# MinimumSystem_Raihansyah_A_M__2150733407.net
KiCad netlist of a schematic drawn in EAGLE
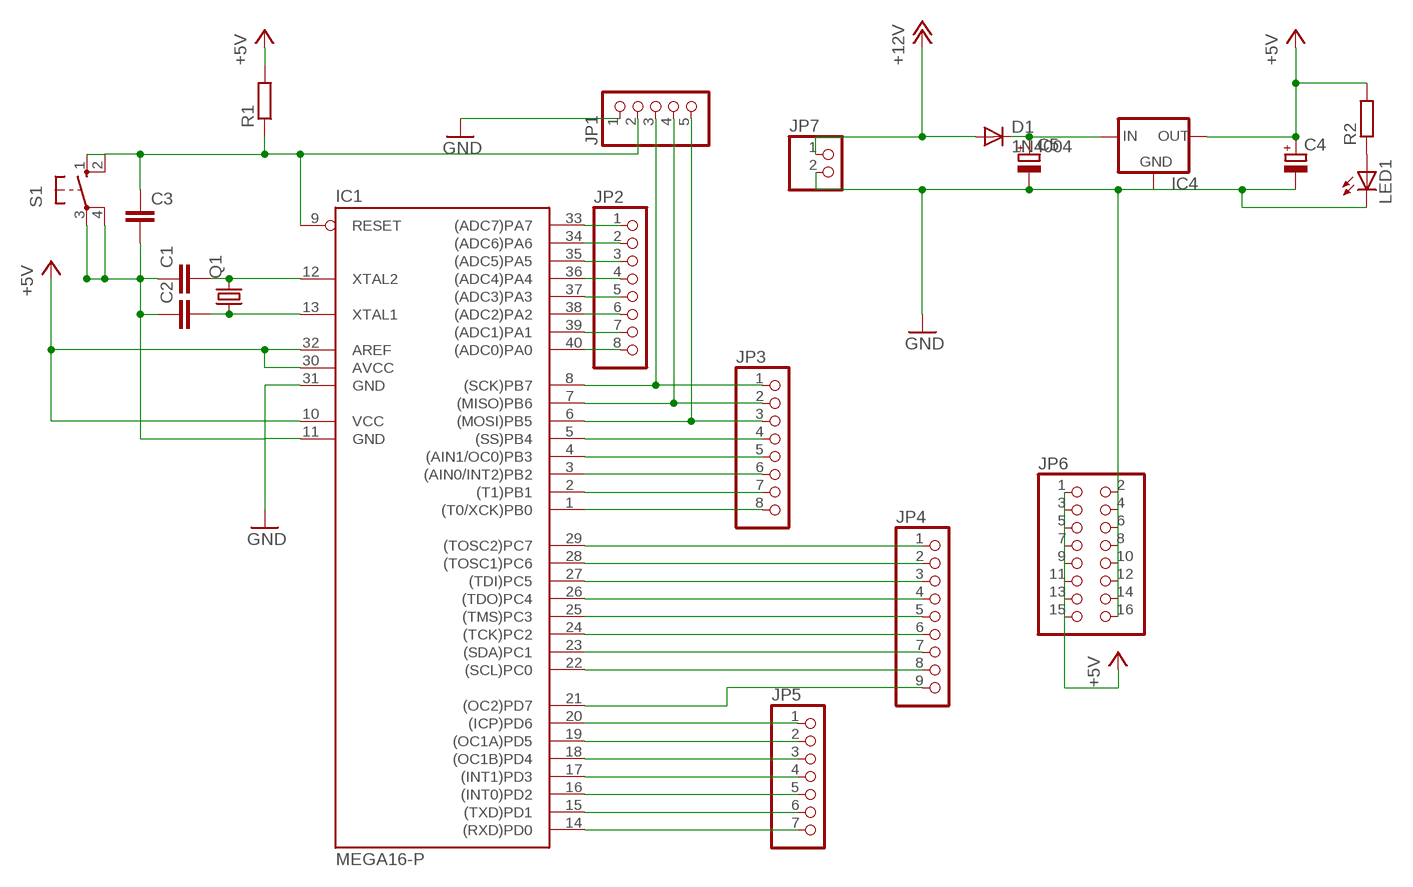
[diagram p0: schematic, sheet 1]

(export (version "E")
  (design (tool "Eeschema 10.0.6"))
  (components
    (comp (ref "C1")
      (value "C-EU025-024X044")
      (footprint "eagle-import:C025-024X044")
      (libsource (lib "eagle-import") (part "C-EU025-024X044"))
    )
    (comp (ref "C2")
      (value "C-EU025-024X044")
      (footprint "eagle-import:C025-024X044")
      (libsource (lib "eagle-import") (part "C-EU025-024X044"))
    )
    (comp (ref "C3")
      (value "C-EU050-025X075")
      (footprint "eagle-import:C050-025X075")
      (libsource (lib "eagle-import") (part "resistor_C-EU050-025X075"))
    )
    (comp (ref "C4")
      (value "CPOL-EUE2.5-5")
      (footprint "eagle-import:E2,5-5")
      (libsource (lib "eagle-import") (part "CPOL-EUE2.5-5"))
    )
    (comp (ref "C5")
      (value "CPOL-EUE2.5-5")
      (footprint "eagle-import:E2,5-5")
      (libsource (lib "eagle-import") (part "CPOL-EUE2.5-5"))
    )
    (comp (ref "D1")
      (value "1N4004")
      (footprint "eagle-import:DO41-10")
      (libsource (lib "eagle-import") (part "1N4004"))
    )
    (comp (ref "IC1")
      (value "MEGA16-P")
      (footprint "eagle-import:DIL40")
      (fields (field (name "MPN") "ATMEGA16-16PU"))
      (libsource (lib "eagle-import") (part "MEGA16-P"))
    )
    (comp (ref "IC4")
      (value "78XXS")
      (footprint "eagle-import:78XXS")
      (libsource (lib "eagle-import") (part "78XXS"))
    )
    (comp (ref "JP1")
      (value "PINHD-1X5")
      (footprint "eagle-import:1X05")
      (libsource (lib "eagle-import") (part "PINHD-1X5"))
    )
    (comp (ref "JP2")
      (value "PINHD-1X8")
      (footprint "eagle-import:1X08")
      (libsource (lib "eagle-import") (part "PINHD-1X8"))
    )
    (comp (ref "JP3")
      (value "PINHD-1X8")
      (footprint "eagle-import:1X08")
      (libsource (lib "eagle-import") (part "PINHD-1X8"))
    )
    (comp (ref "JP4")
      (value "PINHD-1X9")
      (footprint "eagle-import:1X09")
      (libsource (lib "eagle-import") (part "PINHD-1X9"))
    )
    (comp (ref "JP5")
      (value "PINHD-1X7")
      (footprint "eagle-import:1X07")
      (libsource (lib "eagle-import") (part "PINHD-1X7"))
    )
    (comp (ref "JP6")
      (value "PINHD-2X8")
      (footprint "eagle-import:2X08")
      (libsource (lib "eagle-import") (part "PINHD-2X8"))
    )
    (comp (ref "JP7")
      (value "PINHD-1X2")
      (footprint "eagle-import:1X02")
      (libsource (lib "eagle-import") (part "PINHD-1X2"))
    )
    (comp (ref "LED1")
      (value "LED5MM")
      (footprint "eagle-import:LED5MM")
      (libsource (lib "eagle-import") (part "LED5MM"))
    )
    (comp (ref "Q1")
      (value "CRYSTALHC49U-V")
      (footprint "eagle-import:HC49U-V")
      (libsource (lib "eagle-import") (part "CRYSTALHC49U-V"))
    )
    (comp (ref "R1")
      (value "R-EU_0204/7")
      (footprint "eagle-import:0204_7")
      (libsource (lib "eagle-import") (part "R-EU_0204/7"))
    )
    (comp (ref "R2")
      (value "R-EU_0204/7")
      (footprint "eagle-import:0204_7")
      (libsource (lib "eagle-import") (part "R-EU_0204/7"))
    )
    (comp (ref "S1")
      (value "10-XX")
      (footprint "eagle-import:B3F-10XX")
      (fields (field (name "MPN") "B3F-1000"))
      (libsource (lib "eagle-import") (part "10-XX"))
    )
  )
  (nets
    (net (code "1") (name "+5V") (class "Default")
      (node (ref "C4") (pin "+") (pinfunction "+_+") (pintype "passive"))
      (node (ref "IC1") (pin "10") (pinfunction "VCC_10") (pintype "power_in"))
      (node (ref "IC1") (pin "30") (pinfunction "AVCC_30") (pintype "power_in"))
      (node (ref "IC1") (pin "32") (pinfunction "AREF_32") (pintype "passive"))
      (node (ref "IC4") (pin "OUT") (pinfunction "OUT_OUT") (pintype "passive"))
      (node (ref "JP6") (pin "1") (pinfunction "1_1") (pintype "passive"))
      (node (ref "JP6") (pin "11") (pinfunction "11_11") (pintype "passive"))
      (node (ref "JP6") (pin "13") (pinfunction "13_13") (pintype "passive"))
      (node (ref "JP6") (pin "15") (pinfunction "15_15") (pintype "passive"))
      (node (ref "JP6") (pin "3") (pinfunction "3_3") (pintype "passive"))
      (node (ref "JP6") (pin "5") (pinfunction "5_5") (pintype "passive"))
      (node (ref "JP6") (pin "7") (pinfunction "7_7") (pintype "passive"))
      (node (ref "JP6") (pin "9") (pinfunction "9_9") (pintype "passive"))
      (node (ref "R1") (pin "2") (pinfunction "2_2") (pintype "passive"))
      (node (ref "R2") (pin "2") (pinfunction "2_2") (pintype "passive"))
    )
    (net (code "2") (name "+12V") (class "Default")
      (node (ref "D1") (pin "A") (pinfunction "A_A") (pintype "passive"))
      (node (ref "JP7") (pin "1") (pinfunction "1_1") (pintype "passive"))
    )
    (net (code "3") (name "GND") (class "Default")
      (node (ref "C1") (pin "1") (pinfunction "1_1") (pintype "passive"))
      (node (ref "C2") (pin "1") (pinfunction "1_1") (pintype "passive"))
      (node (ref "C3") (pin "2") (pinfunction "2_2") (pintype "passive"))
      (node (ref "C4") (pin "-") (pinfunction "-_-") (pintype "passive"))
      (node (ref "C5") (pin "-") (pinfunction "-_-") (pintype "passive"))
      (node (ref "IC1") (pin "11") (pinfunction "GND_11") (pintype "power_in"))
      (node (ref "IC1") (pin "31") (pinfunction "GND_31") (pintype "power_in"))
      (node (ref "IC4") (pin "GND") (pinfunction "GND_GND") (pintype "input"))
      (node (ref "JP1") (pin "1") (pinfunction "1_1") (pintype "passive"))
      (node (ref "JP6") (pin "10") (pinfunction "10_10") (pintype "passive"))
      (node (ref "JP6") (pin "12") (pinfunction "12_12") (pintype "passive"))
      (node (ref "JP6") (pin "14") (pinfunction "14_14") (pintype "passive"))
      (node (ref "JP6") (pin "16") (pinfunction "16_16") (pintype "passive"))
      (node (ref "JP6") (pin "2") (pinfunction "2_2") (pintype "passive"))
      (node (ref "JP6") (pin "4") (pinfunction "4_4") (pintype "passive"))
      (node (ref "JP6") (pin "6") (pinfunction "6_6") (pintype "passive"))
      (node (ref "JP6") (pin "8") (pinfunction "8_8") (pintype "passive"))
      (node (ref "JP7") (pin "2") (pinfunction "2_2") (pintype "passive"))
      (node (ref "LED1") (pin "K") (pinfunction "C_K") (pintype "passive"))
      (node (ref "S1") (pin "3") (pinfunction "P_3") (pintype "passive"))
      (node (ref "S1") (pin "4") (pinfunction "P1_4") (pintype "passive"))
    )
    (net (code "4") (name "Net-(C5-Pad+)") (class "Default")
      (node (ref "C5") (pin "+") (pinfunction "+_+") (pintype "passive"))
      (node (ref "D1") (pin "C") (pinfunction "C_C") (pintype "passive"))
      (node (ref "IC4") (pin "IN") (pinfunction "IN_IN") (pintype "input"))
    )
    (net (code "5") (name "Net-(IC1-(ADC0)PA0)") (class "Default")
      (node (ref "IC1") (pin "40") (pinfunction "(ADC0)PA0_40") (pintype "bidirectional"))
      (node (ref "JP2") (pin "8") (pinfunction "8_8") (pintype "passive"))
    )
    (net (code "6") (name "Net-(IC1-(ADC1)PA1)") (class "Default")
      (node (ref "IC1") (pin "39") (pinfunction "(ADC1)PA1_39") (pintype "bidirectional"))
      (node (ref "JP2") (pin "7") (pinfunction "7_7") (pintype "passive"))
    )
    (net (code "7") (name "Net-(IC1-(ADC2)PA2)") (class "Default")
      (node (ref "IC1") (pin "38") (pinfunction "(ADC2)PA2_38") (pintype "bidirectional"))
      (node (ref "JP2") (pin "6") (pinfunction "6_6") (pintype "passive"))
    )
    (net (code "8") (name "Net-(IC1-(ADC3)PA3)") (class "Default")
      (node (ref "IC1") (pin "37") (pinfunction "(ADC3)PA3_37") (pintype "bidirectional"))
      (node (ref "JP2") (pin "5") (pinfunction "5_5") (pintype "passive"))
    )
    (net (code "9") (name "Net-(IC1-(ADC4)PA4)") (class "Default")
      (node (ref "IC1") (pin "36") (pinfunction "(ADC4)PA4_36") (pintype "bidirectional"))
      (node (ref "JP2") (pin "4") (pinfunction "4_4") (pintype "passive"))
    )
    (net (code "10") (name "Net-(IC1-(ADC5)PA5)") (class "Default")
      (node (ref "IC1") (pin "35") (pinfunction "(ADC5)PA5_35") (pintype "bidirectional"))
      (node (ref "JP2") (pin "3") (pinfunction "3_3") (pintype "passive"))
    )
    (net (code "11") (name "Net-(IC1-(ADC6)PA6)") (class "Default")
      (node (ref "IC1") (pin "34") (pinfunction "(ADC6)PA6_34") (pintype "bidirectional"))
      (node (ref "JP2") (pin "2") (pinfunction "2_2") (pintype "passive"))
    )
    (net (code "12") (name "Net-(IC1-(ADC7)PA7)") (class "Default")
      (node (ref "IC1") (pin "33") (pinfunction "(ADC7)PA7_33") (pintype "bidirectional"))
      (node (ref "JP2") (pin "1") (pinfunction "1_1") (pintype "passive"))
    )
    (net (code "13") (name "Net-(IC1-(AIN0{slash}INT2)PB2)") (class "Default")
      (node (ref "IC1") (pin "3") (pinfunction "(AIN0/INT2)PB2_3") (pintype "bidirectional"))
      (node (ref "JP3") (pin "6") (pinfunction "6_6") (pintype "passive"))
    )
    (net (code "14") (name "Net-(IC1-(AIN1{slash}OC0)PB3)") (class "Default")
      (node (ref "IC1") (pin "4") (pinfunction "(AIN1/OC0)PB3_4") (pintype "bidirectional"))
      (node (ref "JP3") (pin "5") (pinfunction "5_5") (pintype "passive"))
    )
    (net (code "15") (name "Net-(IC1-(ICP)PD6)") (class "Default")
      (node (ref "IC1") (pin "20") (pinfunction "(ICP)PD6_20") (pintype "bidirectional"))
      (node (ref "JP5") (pin "1") (pinfunction "1_1") (pintype "passive"))
    )
    (net (code "16") (name "Net-(IC1-(INT0)PD2)") (class "Default")
      (node (ref "IC1") (pin "16") (pinfunction "(INT0)PD2_16") (pintype "bidirectional"))
      (node (ref "JP5") (pin "5") (pinfunction "5_5") (pintype "passive"))
    )
    (net (code "17") (name "Net-(IC1-(INT1)PD3)") (class "Default")
      (node (ref "IC1") (pin "17") (pinfunction "(INT1)PD3_17") (pintype "bidirectional"))
      (node (ref "JP5") (pin "4") (pinfunction "4_4") (pintype "passive"))
    )
    (net (code "18") (name "Net-(IC1-(MISO)PB6)") (class "Default")
      (node (ref "IC1") (pin "7") (pinfunction "(MISO)PB6_7") (pintype "bidirectional"))
      (node (ref "JP1") (pin "4") (pinfunction "4_4") (pintype "passive"))
      (node (ref "JP3") (pin "2") (pinfunction "2_2") (pintype "passive"))
    )
    (net (code "19") (name "Net-(IC1-(MOSI)PB5)") (class "Default")
      (node (ref "IC1") (pin "6") (pinfunction "(MOSI)PB5_6") (pintype "bidirectional"))
      (node (ref "JP1") (pin "5") (pinfunction "5_5") (pintype "passive"))
      (node (ref "JP3") (pin "3") (pinfunction "3_3") (pintype "passive"))
    )
    (net (code "20") (name "Net-(IC1-(OC1A)PD5)") (class "Default")
      (node (ref "IC1") (pin "19") (pinfunction "(OC1A)PD5_19") (pintype "bidirectional"))
      (node (ref "JP5") (pin "2") (pinfunction "2_2") (pintype "passive"))
    )
    (net (code "21") (name "Net-(IC1-(OC1B)PD4)") (class "Default")
      (node (ref "IC1") (pin "18") (pinfunction "(OC1B)PD4_18") (pintype "bidirectional"))
      (node (ref "JP5") (pin "3") (pinfunction "3_3") (pintype "passive"))
    )
    (net (code "22") (name "Net-(IC1-(OC2)PD7)") (class "Default")
      (node (ref "IC1") (pin "21") (pinfunction "(OC2)PD7_21") (pintype "bidirectional"))
      (node (ref "JP4") (pin "9") (pinfunction "9_9") (pintype "passive"))
    )
    (net (code "23") (name "Net-(IC1-(RXD)PD0)") (class "Default")
      (node (ref "IC1") (pin "14") (pinfunction "(RXD)PD0_14") (pintype "bidirectional"))
      (node (ref "JP5") (pin "7") (pinfunction "7_7") (pintype "passive"))
    )
    (net (code "24") (name "Net-(IC1-(SCK)PB7)") (class "Default")
      (node (ref "IC1") (pin "8") (pinfunction "(SCK)PB7_8") (pintype "bidirectional"))
      (node (ref "JP1") (pin "3") (pinfunction "3_3") (pintype "passive"))
      (node (ref "JP3") (pin "1") (pinfunction "1_1") (pintype "passive"))
    )
    (net (code "25") (name "Net-(IC1-(SCL)PC0)") (class "Default")
      (node (ref "IC1") (pin "22") (pinfunction "(SCL)PC0_22") (pintype "bidirectional"))
      (node (ref "JP4") (pin "8") (pinfunction "8_8") (pintype "passive"))
    )
    (net (code "26") (name "Net-(IC1-(SDA)PC1)") (class "Default")
      (node (ref "IC1") (pin "23") (pinfunction "(SDA)PC1_23") (pintype "bidirectional"))
      (node (ref "JP4") (pin "7") (pinfunction "7_7") (pintype "passive"))
    )
    (net (code "27") (name "Net-(IC1-(SS)PB4)") (class "Default")
      (node (ref "IC1") (pin "5") (pinfunction "(SS)PB4_5") (pintype "bidirectional"))
      (node (ref "JP3") (pin "4") (pinfunction "4_4") (pintype "passive"))
    )
    (net (code "28") (name "Net-(IC1-(T0{slash}XCK)PB0)") (class "Default")
      (node (ref "IC1") (pin "1") (pinfunction "(T0/XCK)PB0_1") (pintype "bidirectional"))
      (node (ref "JP3") (pin "8") (pinfunction "8_8") (pintype "passive"))
    )
    (net (code "29") (name "Net-(IC1-(T1)PB1)") (class "Default")
      (node (ref "IC1") (pin "2") (pinfunction "(T1)PB1_2") (pintype "bidirectional"))
      (node (ref "JP3") (pin "7") (pinfunction "7_7") (pintype "passive"))
    )
    (net (code "30") (name "Net-(IC1-(TCK)PC2)") (class "Default")
      (node (ref "IC1") (pin "24") (pinfunction "(TCK)PC2_24") (pintype "bidirectional"))
      (node (ref "JP4") (pin "6") (pinfunction "6_6") (pintype "passive"))
    )
    (net (code "31") (name "Net-(IC1-(TDI)PC5)") (class "Default")
      (node (ref "IC1") (pin "27") (pinfunction "(TDI)PC5_27") (pintype "bidirectional"))
      (node (ref "JP4") (pin "3") (pinfunction "3_3") (pintype "passive"))
    )
    (net (code "32") (name "Net-(IC1-(TDO)PC4)") (class "Default")
      (node (ref "IC1") (pin "26") (pinfunction "(TDO)PC4_26") (pintype "bidirectional"))
      (node (ref "JP4") (pin "4") (pinfunction "4_4") (pintype "passive"))
    )
    (net (code "33") (name "Net-(IC1-(TMS)PC3)") (class "Default")
      (node (ref "IC1") (pin "25") (pinfunction "(TMS)PC3_25") (pintype "bidirectional"))
      (node (ref "JP4") (pin "5") (pinfunction "5_5") (pintype "passive"))
    )
    (net (code "34") (name "Net-(IC1-(TOSC1)PC6)") (class "Default")
      (node (ref "IC1") (pin "28") (pinfunction "(TOSC1)PC6_28") (pintype "bidirectional"))
      (node (ref "JP4") (pin "2") (pinfunction "2_2") (pintype "passive"))
    )
    (net (code "35") (name "Net-(IC1-(TOSC2)PC7)") (class "Default")
      (node (ref "IC1") (pin "29") (pinfunction "(TOSC2)PC7_29") (pintype "bidirectional"))
      (node (ref "JP4") (pin "1") (pinfunction "1_1") (pintype "passive"))
    )
    (net (code "36") (name "Net-(IC1-(TXD)PD1)") (class "Default")
      (node (ref "IC1") (pin "15") (pinfunction "(TXD)PD1_15") (pintype "bidirectional"))
      (node (ref "JP5") (pin "6") (pinfunction "6_6") (pintype "passive"))
    )
    (net (code "37") (name "Net-(IC1-RESET)") (class "Default")
      (node (ref "C3") (pin "1") (pinfunction "1_1") (pintype "passive"))
      (node (ref "IC1") (pin "9") (pinfunction "RESET_9") (pintype "input"))
      (node (ref "JP1") (pin "2") (pinfunction "2_2") (pintype "passive"))
      (node (ref "R1") (pin "1") (pinfunction "1_1") (pintype "passive"))
      (node (ref "S1") (pin "1") (pinfunction "S_1") (pintype "passive"))
      (node (ref "S1") (pin "2") (pinfunction "S1_2") (pintype "passive"))
    )
    (net (code "38") (name "Net-(IC1-XTAL1)") (class "Default")
      (node (ref "C2") (pin "2") (pinfunction "2_2") (pintype "passive"))
      (node (ref "IC1") (pin "13") (pinfunction "XTAL1_13") (pintype "bidirectional"))
      (node (ref "Q1") (pin "1") (pinfunction "1_1") (pintype "passive"))
    )
    (net (code "39") (name "Net-(IC1-XTAL2)") (class "Default")
      (node (ref "C1") (pin "2") (pinfunction "2_2") (pintype "passive"))
      (node (ref "IC1") (pin "12") (pinfunction "XTAL2_12") (pintype "bidirectional"))
      (node (ref "Q1") (pin "2") (pinfunction "2_2") (pintype "passive"))
    )
    (net (code "40") (name "Net-(LED1-PadA)") (class "Default")
      (node (ref "LED1") (pin "A") (pinfunction "A_A") (pintype "passive"))
      (node (ref "R2") (pin "1") (pinfunction "1_1") (pintype "passive"))
    )
  )
)
